# Napajanje.net
KiCad netlist of a schematic drawn in Altium Designer
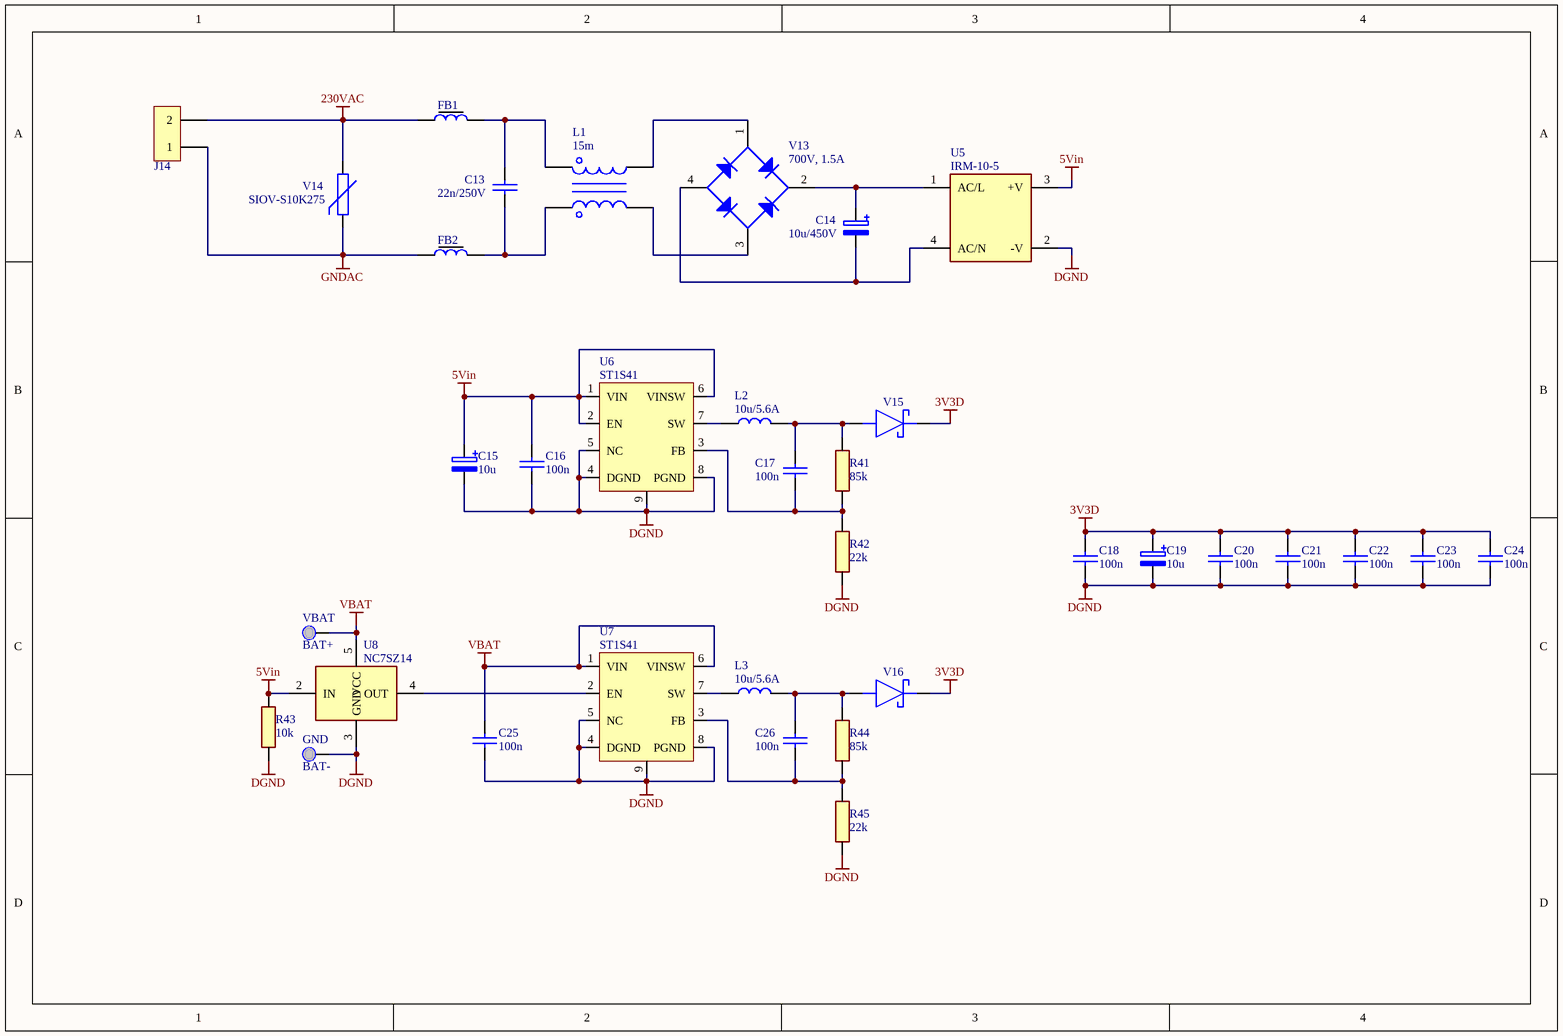
[diagram p0: Napajanje.SchDoc]

(export (version "E")
  (design (tool "Eeschema 10.0.6"))
  (components
    (comp (ref "BAT+")
      (value "VBAT")
      (footprint "PAD_th")
      (description "Single pad")
      (libsource (lib "ShemaLibrary_IEL") (part "PAD"))
    )
    (comp (ref "BAT-")
      (value "GND")
      (footprint "PAD_th")
      (description "Single pad")
      (libsource (lib "ShemaLibrary_IEL") (part "PAD"))
    )
    (comp (ref "C13")
      (value "22n/250V")
      (footprint "CAP_CK03_TH")
      (description "MKX2AW24702F00KSSD")
      (fields (field (name "MOUSER2 PART NUMBER") "505-MKX2AW24702F00KS"))
      (libsource (lib "Moj_lib") (part "CAP_CK03"))
    )
    (comp (ref "C14")
      (value "10u/450V")
      (footprint "CAP_EL_ALU")
      (description "ELECTROLYTIC TH, CASE B")
      (libsource (lib "Moj_lib") (part "CAP_EL"))
    )
    (comp (ref "C15")
      (value "10u")
      (footprint "CAP_EL_CASE_B_SMD")
      (description "ELECTROLYTIC TH, CASE B")
      (libsource (lib "Moj_lib") (part "CAP_EL"))
    )
    (comp (ref "C16")
      (value "100n")
      (footprint "CAP_0805_SMD")
      (description "0805")
      (libsource (lib "Moj_lib") (part "CAP"))
    )
    (comp (ref "C17")
      (value "100n")
      (footprint "CAP_0805_SMD")
      (description "0805")
      (libsource (lib "Moj_lib") (part "CAP"))
    )
    (comp (ref "C18")
      (value "100n")
      (footprint "CAP_0805_SMD")
      (description "0805")
      (libsource (lib "Moj_lib") (part "CAP"))
    )
    (comp (ref "C19")
      (value "10u")
      (footprint "CAP_EL_CASE_B_SMD")
      (description "ELECTROLYTIC TH, CASE B")
      (libsource (lib "Moj_lib") (part "CAP_EL"))
    )
    (comp (ref "C20")
      (value "100n")
      (footprint "CAP_0805_SMD")
      (description "0805")
      (libsource (lib "Moj_lib") (part "CAP"))
    )
    (comp (ref "C21")
      (value "100n")
      (footprint "CAP_0805_SMD")
      (description "0805")
      (libsource (lib "Moj_lib") (part "CAP"))
    )
    (comp (ref "C22")
      (value "100n")
      (footprint "CAP_0805_SMD")
      (description "0805")
      (libsource (lib "Moj_lib") (part "CAP"))
    )
    (comp (ref "C23")
      (value "100n")
      (footprint "CAP_0805_SMD")
      (description "0805")
      (libsource (lib "Moj_lib") (part "CAP"))
    )
    (comp (ref "C24")
      (value "100n")
      (footprint "CAP_0805_SMD")
      (description "0805")
      (libsource (lib "Moj_lib") (part "CAP"))
    )
    (comp (ref "C25")
      (value "100n")
      (footprint "CAP_0805_SMD")
      (description "0805")
      (libsource (lib "Moj_lib") (part "CAP"))
    )
    (comp (ref "C26")
      (value "100n")
      (footprint "CAP_0805_SMD")
      (description "0805")
      (libsource (lib "Moj_lib") (part "CAP"))
    )
    (comp (ref "FB1")
      (value "~")
      (footprint "FERITE_BEAD")
      (description "875-HI1206N101R")
      (libsource (lib "Moj_lib") (part "FERITE_BEAD"))
    )
    (comp (ref "FB2")
      (value "~")
      (footprint "FERITE_BEAD")
      (description "875-HI1206N101R")
      (libsource (lib "Moj_lib") (part "FERITE_BEAD"))
    )
    (comp (ref "J14")
      (value "CON2")
      (footprint "CON-MSTB-5.08-2p")
      (description "2 pole connector")
      (libsource (lib "Moj_Lib") (part "CON2"))
    )
    (comp (ref "L1")
      (value "15m")
      (footprint "CHOKE_10_12.5")
      (description "871-B82731M290")
      (libsource (lib "Moj_lib") (part "CHOKE"))
    )
    (comp (ref "L2")
      (value "10u/5.6A")
      (footprint "PIS4720")
      (description "Inductor")
      (libsource (lib "Moj_lib") (part "INDUCTOR"))
    )
    (comp (ref "L3")
      (value "10u/5.6A")
      (footprint "PIS4720")
      (description "Inductor")
      (libsource (lib "Moj_lib") (part "INDUCTOR"))
    )
    (comp (ref "R41")
      (value "85k")
      (footprint "RES_0805_SMD")
      (description "0805")
      (libsource (lib "Moj_lib") (part "RES"))
    )
    (comp (ref "R42")
      (value "22k")
      (footprint "RES_0805_SMD")
      (description "0805")
      (libsource (lib "Moj_lib") (part "RES"))
    )
    (comp (ref "R43")
      (value "10k")
      (footprint "RES_0805_SMD")
      (description "0805")
      (libsource (lib "Moj_lib") (part "RES"))
    )
    (comp (ref "R44")
      (value "85k")
      (footprint "RES_0805_SMD")
      (description "0805")
      (libsource (lib "Moj_lib") (part "RES"))
    )
    (comp (ref "R45")
      (value "22k")
      (footprint "RES_0805_SMD")
      (description "0805")
      (libsource (lib "Moj_lib") (part "RES"))
    )
    (comp (ref "U5")
      (value "IRM-10-5")
      (footprint "IRM-10-5")
      (description "AC-DC converter")
      (libsource (lib "Moj_lib") (part "IRM-10-5"))
    )
    (comp (ref "U6")
      (value "ST1S41")
      (footprint "ST1S41")
      (description "DC-DC Buck convertor")
      (libsource (lib "Moj_lib") (part "ST1S41"))
    )
    (comp (ref "U7")
      (value "ST1S41")
      (footprint "ST1S41")
      (description "DC-DC Buck convertor")
      (libsource (lib "Moj_lib") (part "ST1S41"))
    )
    (comp (ref "U8")
      (value "NC7SZ14")
      (footprint "NC7SZ14")
      (description "Invertor")
      (libsource (lib "Moj_lib") (part "NC7SZ14"))
    )
    (comp (ref "V13")
      (value "700V, 1.5A")
      (footprint "GRETZ")
      (description "W10G")
      (libsource (lib "Moj_lib") (part "GRETZ"))
    )
    (comp (ref "V14")
      (value "SIOV-S10K275")
      (footprint "VARISTOR")
      (description "Varistor")
      (libsource (lib "Moj_lib") (part "VARISTOR"))
    )
    (comp (ref "V15")
      (value "DIODE SCHOTTKY")
      (footprint "DIODE-SCHOTTKY")
      (description "Schottky diode")
      (libsource (lib "Moj_lib") (part "DIODE SCHOTTKY"))
    )
    (comp (ref "V16")
      (value "DIODE SCHOTTKY")
      (footprint "DIODE-SCHOTTKY")
      (description "Schottky diode")
      (libsource (lib "Moj_lib") (part "DIODE SCHOTTKY"))
    )
  )
  (nets
    (net (code "1") (name "3V3D") (class "Default")
      (node (ref "C18") (pin "2") (pinfunction "2_2") (pintype "passive"))
      (node (ref "C19") (pin "1") (pinfunction "1_1") (pintype "passive"))
      (node (ref "C20") (pin "2") (pinfunction "2_2") (pintype "passive"))
      (node (ref "C21") (pin "2") (pinfunction "2_2") (pintype "passive"))
      (node (ref "C22") (pin "2") (pinfunction "2_2") (pintype "passive"))
      (node (ref "C23") (pin "2") (pinfunction "2_2") (pintype "passive"))
      (node (ref "C24") (pin "2") (pinfunction "2_2") (pintype "passive"))
      (node (ref "V15") (pin "1") (pinfunction "K_1") (pintype "passive"))
      (node (ref "V16") (pin "1") (pinfunction "K_1") (pintype "passive"))
    )
    (net (code "2") (name "5Vin") (class "Default")
      (node (ref "C15") (pin "1") (pinfunction "1_1") (pintype "passive"))
      (node (ref "C16") (pin "2") (pinfunction "2_2") (pintype "passive"))
      (node (ref "R43") (pin "2") (pinfunction "2_2") (pintype "passive"))
      (node (ref "U5") (pin "3") (pinfunction "+V_3") (pintype "passive"))
      (node (ref "U6") (pin "1") (pinfunction "VIN_1") (pintype "passive"))
      (node (ref "U6") (pin "2") (pinfunction "EN_2") (pintype "passive"))
      (node (ref "U6") (pin "6") (pinfunction "VINSW_6") (pintype "passive"))
      (node (ref "U8") (pin "2") (pinfunction "IN_2") (pintype "passive"))
    )
    (net (code "3") (name "230VAC") (class "Default")
      (node (ref "FB1") (pin "1") (pintype "power_in"))
      (node (ref "J14") (pin "2") (pinfunction "2_2") (pintype "passive"))
      (node (ref "V14") (pin "2") (pinfunction "2_2") (pintype "passive"))
    )
    (net (code "4") (name "DGND") (class "Default")
      (node (ref "BAT-") (pin "1") (pintype "passive"))
      (node (ref "C15") (pin "2") (pinfunction "2_2") (pintype "passive"))
      (node (ref "C16") (pin "1") (pinfunction "1_1") (pintype "passive"))
      (node (ref "C18") (pin "1") (pinfunction "1_1") (pintype "passive"))
      (node (ref "C19") (pin "2") (pinfunction "2_2") (pintype "passive"))
      (node (ref "C20") (pin "1") (pinfunction "1_1") (pintype "passive"))
      (node (ref "C21") (pin "1") (pinfunction "1_1") (pintype "passive"))
      (node (ref "C22") (pin "1") (pinfunction "1_1") (pintype "passive"))
      (node (ref "C23") (pin "1") (pinfunction "1_1") (pintype "passive"))
      (node (ref "C24") (pin "1") (pinfunction "1_1") (pintype "passive"))
      (node (ref "C25") (pin "1") (pinfunction "1_1") (pintype "passive"))
      (node (ref "R42") (pin "1") (pinfunction "1_1") (pintype "passive"))
      (node (ref "R43") (pin "1") (pinfunction "1_1") (pintype "passive"))
      (node (ref "R45") (pin "1") (pinfunction "1_1") (pintype "passive"))
      (node (ref "U5") (pin "2") (pinfunction "-V_2") (pintype "passive"))
      (node (ref "U6") (pin "4") (pinfunction "DGND_4") (pintype "passive"))
      (node (ref "U6") (pin "5") (pinfunction "NC_5") (pintype "passive"))
      (node (ref "U6") (pin "8") (pinfunction "PGND_8") (pintype "passive"))
      (node (ref "U6") (pin "9") (pinfunction "DGND_9") (pintype "passive"))
      (node (ref "U7") (pin "4") (pinfunction "DGND_4") (pintype "passive"))
      (node (ref "U7") (pin "5") (pinfunction "NC_5") (pintype "passive"))
      (node (ref "U7") (pin "8") (pinfunction "PGND_8") (pintype "passive"))
      (node (ref "U7") (pin "9") (pinfunction "DGND_9") (pintype "passive"))
      (node (ref "U8") (pin "3") (pinfunction "GND_3") (pintype "passive"))
    )
    (net (code "5") (name "GNDAC") (class "Default")
      (node (ref "FB2") (pin "1") (pintype "power_in"))
      (node (ref "J14") (pin "1") (pinfunction "1_1") (pintype "passive"))
      (node (ref "V14") (pin "1") (pinfunction "1_1") (pintype "passive"))
    )
    (net (code "6") (name "Net-(C13-Pad1)") (class "Default")
      (node (ref "C13") (pin "1") (pinfunction "1_1") (pintype "passive"))
      (node (ref "FB2") (pin "2") (pintype "power_in"))
      (node (ref "L1") (pin "1") (pinfunction "1_1") (pintype "passive"))
    )
    (net (code "7") (name "Net-(C13-Pad2)") (class "Default")
      (node (ref "C13") (pin "2") (pinfunction "2_2") (pintype "passive"))
      (node (ref "FB1") (pin "2") (pintype "power_in"))
      (node (ref "L1") (pin "2") (pinfunction "2_2") (pintype "passive"))
    )
    (net (code "8") (name "Net-(L1-Pad3)") (class "Default")
      (node (ref "L1") (pin "3") (pinfunction "3_3") (pintype "passive"))
      (node (ref "V13") (pin "3") (pinfunction "3_3") (pintype "passive"))
    )
    (net (code "9") (name "Net-(L1-Pad4)") (class "Default")
      (node (ref "L1") (pin "4") (pinfunction "4_4") (pintype "passive"))
      (node (ref "V13") (pin "1") (pinfunction "1_1") (pintype "passive"))
    )
    (net (code "10") (name "Net-(U5-AC{slash}L)") (class "Default")
      (node (ref "C14") (pin "1") (pinfunction "1_1") (pintype "passive"))
      (node (ref "U5") (pin "1") (pinfunction "AC/L_1") (pintype "passive"))
      (node (ref "V13") (pin "2") (pinfunction "2_2") (pintype "passive"))
    )
    (net (code "11") (name "Net-(U5-AC{slash}N)") (class "Default")
      (node (ref "C14") (pin "2") (pinfunction "2_2") (pintype "passive"))
      (node (ref "U5") (pin "4") (pinfunction "AC/N_4") (pintype "passive"))
      (node (ref "V13") (pin "4") (pinfunction "4_4") (pintype "passive"))
    )
    (net (code "12") (name "Net-(U6-FB)") (class "Default")
      (node (ref "C17") (pin "1") (pinfunction "1_1") (pintype "passive"))
      (node (ref "R41") (pin "1") (pinfunction "1_1") (pintype "passive"))
      (node (ref "R42") (pin "2") (pinfunction "2_2") (pintype "passive"))
      (node (ref "U6") (pin "3") (pinfunction "FB_3") (pintype "passive"))
    )
    (net (code "13") (name "Net-(U6-SW)") (class "Default")
      (node (ref "L2") (pin "1") (pintype "power_in"))
      (node (ref "U6") (pin "7") (pinfunction "SW_7") (pintype "passive"))
    )
    (net (code "14") (name "Net-(U7-EN)") (class "Default")
      (node (ref "U7") (pin "2") (pinfunction "EN_2") (pintype "passive"))
      (node (ref "U8") (pin "4") (pinfunction "OUT_4") (pintype "passive"))
    )
    (net (code "15") (name "Net-(U7-FB)") (class "Default")
      (node (ref "C26") (pin "1") (pinfunction "1_1") (pintype "passive"))
      (node (ref "R44") (pin "1") (pinfunction "1_1") (pintype "passive"))
      (node (ref "R45") (pin "2") (pinfunction "2_2") (pintype "passive"))
      (node (ref "U7") (pin "3") (pinfunction "FB_3") (pintype "passive"))
    )
    (net (code "16") (name "Net-(U7-SW)") (class "Default")
      (node (ref "L3") (pin "1") (pintype "power_in"))
      (node (ref "U7") (pin "7") (pinfunction "SW_7") (pintype "passive"))
    )
    (net (code "17") (name "Net-(V15-A)") (class "Default")
      (node (ref "C17") (pin "2") (pinfunction "2_2") (pintype "passive"))
      (node (ref "L2") (pin "2") (pintype "power_in"))
      (node (ref "R41") (pin "2") (pinfunction "2_2") (pintype "passive"))
      (node (ref "V15") (pin "2") (pinfunction "A_2") (pintype "passive"))
    )
    (net (code "18") (name "Net-(V16-A)") (class "Default")
      (node (ref "C26") (pin "2") (pinfunction "2_2") (pintype "passive"))
      (node (ref "L3") (pin "2") (pintype "power_in"))
      (node (ref "R44") (pin "2") (pinfunction "2_2") (pintype "passive"))
      (node (ref "V16") (pin "2") (pinfunction "A_2") (pintype "passive"))
    )
    (net (code "19") (name "VBAT") (class "Default")
      (node (ref "BAT+") (pin "1") (pintype "passive"))
      (node (ref "C25") (pin "2") (pinfunction "2_2") (pintype "passive"))
      (node (ref "U7") (pin "1") (pinfunction "VIN_1") (pintype "passive"))
      (node (ref "U7") (pin "6") (pinfunction "VINSW_6") (pintype "passive"))
      (node (ref "U8") (pin "5") (pinfunction "VCC_5") (pintype "passive"))
    )
  )
)
